# gerbang_fix.net
KiCad netlist of a schematic drawn in EAGLE
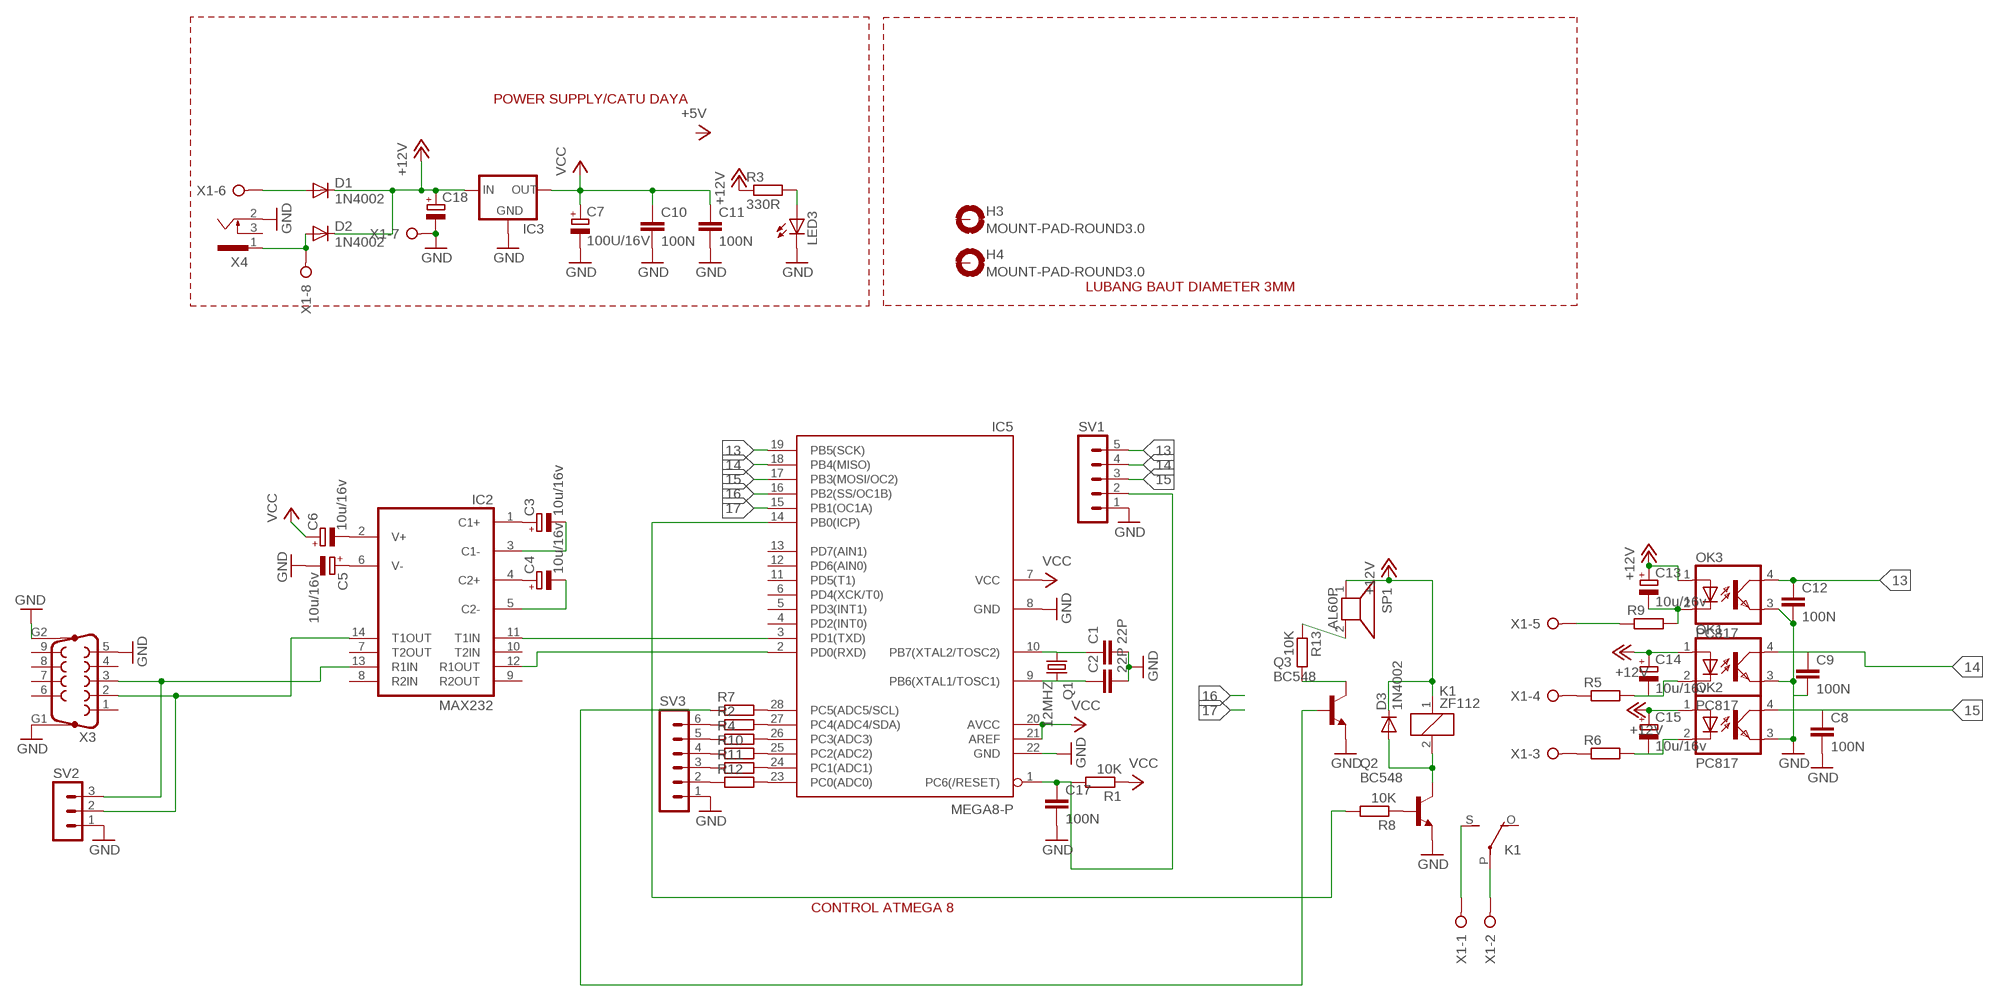
[diagram p0: schematic, sheet 1]

(export (version "E")
  (design (tool "Eeschema 10.0.6"))
  (components
    (comp (ref "C1")
      (value "22P")
      (footprint "eagle-import:C025-025X050")
      (libsource (lib "eagle-import") (part "C-EU025-025X050"))
    )
    (comp (ref "C2")
      (value "22P")
      (footprint "eagle-import:C025-025X050")
      (libsource (lib "eagle-import") (part "C-EU025-025X050"))
    )
    (comp (ref "C3")
      (value "10u/16v")
      (footprint "eagle-import:E2,5-6")
      (libsource (lib "eagle-import") (part "resistor_CPOL-EUE2.5-6"))
    )
    (comp (ref "C4")
      (value "10u/16v")
      (footprint "eagle-import:E2,5-6")
      (libsource (lib "eagle-import") (part "resistor_CPOL-EUE2.5-6"))
    )
    (comp (ref "C5")
      (value "10u/16v")
      (footprint "eagle-import:E2,5-6")
      (libsource (lib "eagle-import") (part "resistor_CPOL-EUE2.5-6"))
    )
    (comp (ref "C6")
      (value "10u/16v")
      (footprint "eagle-import:E2,5-6")
      (libsource (lib "eagle-import") (part "resistor_CPOL-EUE2.5-6"))
    )
    (comp (ref "C7")
      (value "100U/16V")
      (footprint "eagle-import:E2,5-6")
      (libsource (lib "eagle-import") (part "resistor_CPOL-EUE2.5-6"))
    )
    (comp (ref "C8")
      (value "100N")
      (footprint "eagle-import:C025-025X050")
      (libsource (lib "eagle-import") (part "C-EU025-025X050"))
    )
    (comp (ref "C9")
      (value "100N")
      (footprint "eagle-import:C025-025X050")
      (libsource (lib "eagle-import") (part "C-EU025-025X050"))
    )
    (comp (ref "C10")
      (value "100N")
      (footprint "eagle-import:C025-025X050")
      (libsource (lib "eagle-import") (part "C-EU025-025X050"))
    )
    (comp (ref "C11")
      (value "100N")
      (footprint "eagle-import:C025-025X050")
      (libsource (lib "eagle-import") (part "C-EU025-025X050"))
    )
    (comp (ref "C12")
      (value "100N")
      (footprint "eagle-import:C025-025X050")
      (libsource (lib "eagle-import") (part "C-EU025-025X050"))
    )
    (comp (ref "C13")
      (value "10u/16v")
      (footprint "eagle-import:E2,5-6")
      (libsource (lib "eagle-import") (part "resistor_CPOL-EUE2.5-6"))
    )
    (comp (ref "C14")
      (value "10u/16v")
      (footprint "eagle-import:E2,5-6")
      (libsource (lib "eagle-import") (part "resistor_CPOL-EUE2.5-6"))
    )
    (comp (ref "C15")
      (value "10u/16v")
      (footprint "eagle-import:E2,5-6")
      (libsource (lib "eagle-import") (part "resistor_CPOL-EUE2.5-6"))
    )
    (comp (ref "C17")
      (value "100N")
      (footprint "eagle-import:C025-025X050")
      (libsource (lib "eagle-import") (part "C-EU025-025X050"))
    )
    (comp (ref "C18")
      (value "CPOL-EUE5-8.5")
      (footprint "eagle-import:E5-8,5")
      (libsource (lib "eagle-import") (part "CPOL-EUE5-8.5"))
    )
    (comp (ref "D1")
      (value "1N4002")
      (footprint "eagle-import:DO35-10")
      (libsource (lib "eagle-import") (part "1N4148DO35-10"))
    )
    (comp (ref "D2")
      (value "1N4002")
      (footprint "eagle-import:DO35-10")
      (libsource (lib "eagle-import") (part "1N4148DO35-10"))
    )
    (comp (ref "D3")
      (value "1N4002")
      (footprint "eagle-import:DO35-10")
      (libsource (lib "eagle-import") (part "1N4148DO35-10"))
    )
    (comp (ref "H3")
      (value "MOUNT-PAD-ROUND3.0")
      (footprint "eagle-import:3,0-PAD")
      (libsource (lib "eagle-import") (part "MOUNT-PAD-ROUND3.0"))
    )
    (comp (ref "H4")
      (value "MOUNT-PAD-ROUND3.0")
      (footprint "eagle-import:3,0-PAD")
      (libsource (lib "eagle-import") (part "MOUNT-PAD-ROUND3.0"))
    )
    (comp (ref "IC2")
      (value "MAX232")
      (footprint "eagle-import:DIL16")
      (fields (field (name "MF") "MAXIM") (field (name "MPN") "MAX232ACPE+"))
      (libsource (lib "eagle-import") (part "MAX232"))
    )
    (comp (ref "IC3")
      (value "78XXS")
      (footprint "eagle-import:78XXS")
      (libsource (lib "eagle-import") (part "78XXS"))
    )
    (comp (ref "IC5")
      (value "MEGA8-P")
      (footprint "eagle-import:DIL28-3")
      (libsource (lib "eagle-import") (part "MEGA8-P"))
    )
    (comp (ref "K1")
      (value "ZF112")
      (footprint "eagle-import:ZF112")
      (libsource (lib "eagle-import") (part "ZF112"))
    )
    (comp (ref "LED3")
      (value "LED5MM")
      (footprint "eagle-import:LED5MM")
      (libsource (lib "eagle-import") (part "LED5MM"))
    )
    (comp (ref "OK1")
      (value "PC817")
      (footprint "eagle-import:DIL04")
      (fields (field (name "MPN") "PC817X4J000F"))
      (libsource (lib "eagle-import") (part "PC817"))
    )
    (comp (ref "OK2")
      (value "PC817")
      (footprint "eagle-import:DIL04")
      (fields (field (name "MPN") "PC817X4J000F"))
      (libsource (lib "eagle-import") (part "PC817"))
    )
    (comp (ref "OK3")
      (value "PC817")
      (footprint "eagle-import:DIL04")
      (fields (field (name "MPN") "PC817X4J000F"))
      (libsource (lib "eagle-import") (part "PC817"))
    )
    (comp (ref "Q1")
      (value "12MHZ")
      (footprint "eagle-import:HC49U-V")
      (libsource (lib "eagle-import") (part "CRYSTALHC49U-V"))
    )
    (comp (ref "Q2")
      (value "BC548")
      (footprint "eagle-import:TO92-EBC")
      (libsource (lib "eagle-import") (part "BC548"))
    )
    (comp (ref "Q3")
      (value "BC548")
      (footprint "eagle-import:TO92-EBC")
      (libsource (lib "eagle-import") (part "BC548"))
    )
    (comp (ref "R1")
      (value "10K")
      (footprint "eagle-import:0207_10")
      (libsource (lib "eagle-import") (part "resistor_R-EU_0207/10"))
    )
    (comp (ref "R2")
      (value "R-EU_0204/2V")
      (footprint "eagle-import:0204V")
      (libsource (lib "eagle-import") (part "R-EU_0204/2V"))
    )
    (comp (ref "R3")
      (value "330R")
      (footprint "eagle-import:0207_10")
      (libsource (lib "eagle-import") (part "resistor_R-EU_0207/10"))
    )
    (comp (ref "R4")
      (value "R-EU_0204/2V")
      (footprint "eagle-import:0204V")
      (libsource (lib "eagle-import") (part "R-EU_0204/2V"))
    )
    (comp (ref "R5")
      (value "R-EU_0204/2V")
      (footprint "eagle-import:0204V")
      (libsource (lib "eagle-import") (part "R-EU_0204/2V"))
    )
    (comp (ref "R6")
      (value "R-EU_0204/2V")
      (footprint "eagle-import:0204V")
      (libsource (lib "eagle-import") (part "R-EU_0204/2V"))
    )
    (comp (ref "R7")
      (value "R-EU_0204/2V")
      (footprint "eagle-import:0204V")
      (libsource (lib "eagle-import") (part "R-EU_0204/2V"))
    )
    (comp (ref "R8")
      (value "10K")
      (footprint "eagle-import:0207_10")
      (libsource (lib "eagle-import") (part "resistor_R-EU_0207/10"))
    )
    (comp (ref "R9")
      (value "R-EU_0204/2V")
      (footprint "eagle-import:0204V")
      (libsource (lib "eagle-import") (part "R-EU_0204/2V"))
    )
    (comp (ref "R10")
      (value "R-EU_0204/2V")
      (footprint "eagle-import:0204V")
      (libsource (lib "eagle-import") (part "R-EU_0204/2V"))
    )
    (comp (ref "R11")
      (value "R-EU_0204/2V")
      (footprint "eagle-import:0204V")
      (libsource (lib "eagle-import") (part "R-EU_0204/2V"))
    )
    (comp (ref "R12")
      (value "R-EU_0204/2V")
      (footprint "eagle-import:0204V")
      (libsource (lib "eagle-import") (part "R-EU_0204/2V"))
    )
    (comp (ref "R13")
      (value "10K")
      (footprint "eagle-import:0207_10")
      (libsource (lib "eagle-import") (part "resistor_R-EU_0207/10"))
    )
    (comp (ref "SP1")
      (value "AL60P")
      (footprint "eagle-import:AL60P")
      (libsource (lib "eagle-import") (part "AL60P"))
    )
    (comp (ref "SV1")
      (value "MA05-1")
      (footprint "eagle-import:MA05-1")
      (libsource (lib "eagle-import") (part "MA05-1"))
    )
    (comp (ref "SV2")
      (value "MA03-1")
      (footprint "eagle-import:MA03-1")
      (libsource (lib "eagle-import") (part "MA03-1"))
    )
    (comp (ref "SV3")
      (value "MA06-1")
      (footprint "eagle-import:MA06-1")
      (libsource (lib "eagle-import") (part "MA06-1"))
    )
    (comp (ref "X1")
      (value "W237-08P")
      (footprint "eagle-import:W237-8P")
      (libsource (lib "eagle-import") (part "W237-08P"))
    )
    (comp (ref "X3")
      (value "F09HP")
      (footprint "eagle-import:F09HP")
      (libsource (lib "eagle-import") (part "F09HP"))
    )
    (comp (ref "X4")
      (value "733980-62")
      (footprint "eagle-import:733980-62")
      (libsource (lib "eagle-import") (part "73398?0-62"))
    )
  )
  (nets
    (net (code "2") (name "+12V") (class "Default")
      (node (ref "C13") (pin "+") (pinfunction "+_+") (pintype "passive"))
      (node (ref "C14") (pin "+") (pinfunction "+_+") (pintype "passive"))
      (node (ref "C15") (pin "+") (pinfunction "+_+") (pintype "passive"))
      (node (ref "C18") (pin "+") (pinfunction "+_+") (pintype "passive"))
      (node (ref "D1") (pin "C") (pinfunction "C_C") (pintype "passive"))
      (node (ref "D2") (pin "C") (pinfunction "C_C") (pintype "passive"))
      (node (ref "D3") (pin "C") (pinfunction "C_C") (pintype "passive"))
      (node (ref "IC3") (pin "IN") (pinfunction "IN_IN") (pintype "input"))
      (node (ref "K1") (pin "1") (pinfunction "1_1") (pintype "passive"))
      (node (ref "OK1") (pin "1") (pinfunction "A_1") (pintype "passive"))
      (node (ref "OK2") (pin "1") (pinfunction "A_1") (pintype "passive"))
      (node (ref "OK3") (pin "1") (pinfunction "A_1") (pintype "passive"))
      (node (ref "R3") (pin "1") (pinfunction "1_1") (pintype "passive"))
      (node (ref "SP1") (pin "1") (pinfunction "1_1") (pintype "passive"))
    )
    (net (code "3") (name "13") (class "Default")
      (node (ref "C12") (pin "1") (pinfunction "1_1") (pintype "passive"))
      (node (ref "IC5") (pin "19") (pinfunction "PB5(SCK)_19") (pintype "bidirectional"))
      (node (ref "OK3") (pin "4") (pinfunction "COL_4") (pintype "passive"))
      (node (ref "SV1") (pin "5") (pinfunction "5_5") (pintype "passive"))
    )
    (net (code "4") (name "14") (class "Default")
      (node (ref "C9") (pin "1") (pinfunction "1_1") (pintype "passive"))
      (node (ref "IC5") (pin "18") (pinfunction "PB4(MISO)_18") (pintype "bidirectional"))
      (node (ref "OK1") (pin "4") (pinfunction "COL_4") (pintype "passive"))
      (node (ref "SV1") (pin "4") (pinfunction "4_4") (pintype "passive"))
    )
    (net (code "5") (name "15") (class "Default")
      (node (ref "C8") (pin "1") (pinfunction "1_1") (pintype "passive"))
      (node (ref "IC5") (pin "17") (pinfunction "PB3(MOSI/OC2)_17") (pintype "bidirectional"))
      (node (ref "OK2") (pin "4") (pinfunction "COL_4") (pintype "passive"))
      (node (ref "SV1") (pin "3") (pinfunction "3_3") (pintype "passive"))
    )
    (net (code "6") (name "16") (class "Default")
      (node (ref "IC5") (pin "16") (pinfunction "PB2(SS/OC1B)_16") (pintype "bidirectional"))
    )
    (net (code "7") (name "17") (class "Default")
      (node (ref "IC5") (pin "15") (pinfunction "PB1(OC1A)_15") (pintype "bidirectional"))
    )
    (net (code "8") (name "GND") (class "Default")
      (node (ref "C1") (pin "2") (pinfunction "2_2") (pintype "passive"))
      (node (ref "C10") (pin "2") (pinfunction "2_2") (pintype "passive"))
      (node (ref "C11") (pin "2") (pinfunction "2_2") (pintype "passive"))
      (node (ref "C12") (pin "2") (pinfunction "2_2") (pintype "passive"))
      (node (ref "C17") (pin "2") (pinfunction "2_2") (pintype "passive"))
      (node (ref "C18") (pin "-") (pinfunction "-_-") (pintype "passive"))
      (node (ref "C2") (pin "2") (pinfunction "2_2") (pintype "passive"))
      (node (ref "C5") (pin "-") (pinfunction "-_-") (pintype "passive"))
      (node (ref "C7") (pin "-") (pinfunction "-_-") (pintype "passive"))
      (node (ref "C8") (pin "2") (pinfunction "2_2") (pintype "passive"))
      (node (ref "C9") (pin "2") (pinfunction "2_2") (pintype "passive"))
      (node (ref "IC3") (pin "GND") (pinfunction "GND_GND") (pintype "input"))
      (node (ref "IC5") (pin "22") (pinfunction "GND_22") (pintype "power_in"))
      (node (ref "IC5") (pin "8") (pinfunction "GND_8") (pintype "power_in"))
      (node (ref "LED3") (pin "K") (pinfunction "C_K") (pintype "passive"))
      (node (ref "OK1") (pin "3") (pinfunction "EMIT_3") (pintype "passive"))
      (node (ref "OK2") (pin "3") (pinfunction "EMIT_3") (pintype "passive"))
      (node (ref "OK3") (pin "3") (pinfunction "EMIT_3") (pintype "passive"))
      (node (ref "Q2") (pin "E") (pinfunction "E_E") (pintype "passive"))
      (node (ref "Q3") (pin "E") (pinfunction "E_E") (pintype "passive"))
      (node (ref "SV1") (pin "1") (pinfunction "1_1") (pintype "passive"))
      (node (ref "SV2") (pin "1") (pinfunction "1_1") (pintype "passive"))
      (node (ref "SV3") (pin "1") (pinfunction "1_1") (pintype "passive"))
      (node (ref "X1") (pin "7") (pinfunction "KL_7") (pintype "passive"))
      (node (ref "X3") (pin "5") (pinfunction "5_5") (pintype "passive"))
      (node (ref "X3") (pin "G1") (pinfunction "G1_G1") (pintype "passive"))
      (node (ref "X3") (pin "G2") (pinfunction "G2_G2") (pintype "passive"))
      (node (ref "X4") (pin "2") (pinfunction "2_2") (pintype "passive"))
    )
    (net (code "9") (name "Net-(D3-PadA)") (class "Default")
      (node (ref "D3") (pin "A") (pinfunction "A_A") (pintype "passive"))
      (node (ref "K1") (pin "2") (pinfunction "2_2") (pintype "passive"))
      (node (ref "Q2") (pin "C") (pinfunction "C_C") (pintype "passive"))
    )
    (net (code "10") (name "Net-(IC2A-C1+)") (class "Default")
      (node (ref "C3") (pin "+") (pinfunction "+_+") (pintype "passive"))
      (node (ref "IC2") (pin "1") (pinfunction "C1+_1") (pintype "bidirectional"))
    )
    (net (code "11") (name "Net-(IC2A-C1-)") (class "Default")
      (node (ref "C3") (pin "-") (pinfunction "-_-") (pintype "passive"))
      (node (ref "IC2") (pin "3") (pinfunction "C1-_3") (pintype "bidirectional"))
    )
    (net (code "12") (name "Net-(IC2A-C2+)") (class "Default")
      (node (ref "C4") (pin "+") (pinfunction "+_+") (pintype "passive"))
      (node (ref "IC2") (pin "4") (pinfunction "C2+_4") (pintype "bidirectional"))
    )
    (net (code "13") (name "Net-(IC2A-C2-)") (class "Default")
      (node (ref "C4") (pin "-") (pinfunction "-_-") (pintype "passive"))
      (node (ref "IC2") (pin "5") (pinfunction "C2-_5") (pintype "bidirectional"))
    )
    (net (code "14") (name "Net-(IC2A-R1IN)") (class "Default")
      (node (ref "IC2") (pin "13") (pinfunction "R1IN_13") (pintype "input"))
      (node (ref "SV2") (pin "3") (pinfunction "3_3") (pintype "passive"))
      (node (ref "X3") (pin "3") (pinfunction "3_3") (pintype "passive"))
    )
    (net (code "15") (name "Net-(IC2A-R1OUT)") (class "Default")
      (node (ref "IC2") (pin "12") (pinfunction "R1OUT_12") (pintype "output"))
      (node (ref "IC5") (pin "2") (pinfunction "PD0(RXD)_2") (pintype "bidirectional"))
    )
    (net (code "16") (name "Net-(IC2A-T1IN)") (class "Default")
      (node (ref "IC2") (pin "11") (pinfunction "T1IN_11") (pintype "input"))
      (node (ref "IC5") (pin "3") (pinfunction "PD1(TXD)_3") (pintype "bidirectional"))
    )
    (net (code "17") (name "Net-(IC2A-T1OUT)") (class "Default")
      (node (ref "IC2") (pin "14") (pinfunction "T1OUT_14") (pintype "output"))
      (node (ref "SV2") (pin "2") (pinfunction "2_2") (pintype "passive"))
      (node (ref "X3") (pin "2") (pinfunction "2_2") (pintype "passive"))
    )
    (net (code "18") (name "Net-(IC2A-V+)") (class "Default")
      (node (ref "C6") (pin "-") (pinfunction "-_-") (pintype "passive"))
      (node (ref "IC2") (pin "2") (pinfunction "V+_2") (pintype "bidirectional"))
    )
    (net (code "19") (name "Net-(IC2A-V-)") (class "Default")
      (node (ref "C5") (pin "+") (pinfunction "+_+") (pintype "passive"))
      (node (ref "IC2") (pin "6") (pinfunction "V-_6") (pintype "bidirectional"))
    )
    (net (code "20") (name "Net-(IC5-PB0(ICP))") (class "Default")
      (node (ref "IC5") (pin "14") (pinfunction "PB0(ICP)_14") (pintype "bidirectional"))
      (node (ref "R8") (pin "2") (pinfunction "2_2") (pintype "passive"))
    )
    (net (code "21") (name "Net-(IC5-PB6(XTAL1{slash}TOSC1))") (class "Default")
      (node (ref "C2") (pin "1") (pinfunction "1_1") (pintype "passive"))
      (node (ref "IC5") (pin "9") (pinfunction "PB6(XTAL1/TOSC1)_9") (pintype "bidirectional"))
      (node (ref "Q1") (pin "2") (pinfunction "2_2") (pintype "passive"))
    )
    (net (code "22") (name "Net-(IC5-PB7(XTAL2{slash}TOSC2))") (class "Default")
      (node (ref "C1") (pin "1") (pinfunction "1_1") (pintype "passive"))
      (node (ref "IC5") (pin "10") (pinfunction "PB7(XTAL2/TOSC2)_10") (pintype "bidirectional"))
      (node (ref "Q1") (pin "1") (pinfunction "1_1") (pintype "passive"))
    )
    (net (code "23") (name "Net-(IC5-PC0(ADC0))") (class "Default")
      (node (ref "IC5") (pin "23") (pinfunction "PC0(ADC0)_23") (pintype "bidirectional"))
      (node (ref "R12") (pin "2") (pinfunction "2_2") (pintype "passive"))
    )
    (net (code "24") (name "Net-(IC5-PC1(ADC1))") (class "Default")
      (node (ref "IC5") (pin "24") (pinfunction "PC1(ADC1)_24") (pintype "bidirectional"))
      (node (ref "R11") (pin "2") (pinfunction "2_2") (pintype "passive"))
    )
    (net (code "25") (name "Net-(IC5-PC2(ADC2))") (class "Default")
      (node (ref "IC5") (pin "25") (pinfunction "PC2(ADC2)_25") (pintype "bidirectional"))
      (node (ref "R10") (pin "2") (pinfunction "2_2") (pintype "passive"))
    )
    (net (code "26") (name "Net-(IC5-PC3(ADC3))") (class "Default")
      (node (ref "IC5") (pin "26") (pinfunction "PC3(ADC3)_26") (pintype "bidirectional"))
      (node (ref "R4") (pin "2") (pinfunction "2_2") (pintype "passive"))
    )
    (net (code "27") (name "Net-(IC5-PC4(ADC4{slash}SDA))") (class "Default")
      (node (ref "IC5") (pin "27") (pinfunction "PC4(ADC4/SDA)_27") (pintype "bidirectional"))
      (node (ref "R2") (pin "2") (pinfunction "2_2") (pintype "passive"))
    )
    (net (code "28") (name "Net-(IC5-PC5(ADC5{slash}SCL))") (class "Default")
      (node (ref "IC5") (pin "28") (pinfunction "PC5(ADC5/SCL)_28") (pintype "bidirectional"))
      (node (ref "R7") (pin "2") (pinfunction "2_2") (pintype "passive"))
    )
    (net (code "29") (name "Net-(IC5-PC6({slash}RESET))") (class "Default")
      (node (ref "C17") (pin "1") (pinfunction "1_1") (pintype "passive"))
      (node (ref "IC5") (pin "1") (pinfunction "PC6(/RESET)_1") (pintype "bidirectional"))
      (node (ref "R1") (pin "2") (pinfunction "2_2") (pintype "passive"))
      (node (ref "SV1") (pin "2") (pinfunction "2_2") (pintype "passive"))
    )
    (net (code "30") (name "Net-(LED3-PadA)") (class "Default")
      (node (ref "LED3") (pin "A") (pinfunction "A_A") (pintype "passive"))
      (node (ref "R3") (pin "2") (pinfunction "2_2") (pintype "passive"))
    )
    (net (code "31") (name "Net-(OK1-C)") (class "Default")
      (node (ref "C14") (pin "-") (pinfunction "-_-") (pintype "passive"))
      (node (ref "OK1") (pin "2") (pinfunction "C_2") (pintype "passive"))
      (node (ref "R5") (pin "2") (pinfunction "2_2") (pintype "passive"))
    )
    (net (code "32") (name "Net-(OK2-C)") (class "Default")
      (node (ref "C15") (pin "-") (pinfunction "-_-") (pintype "passive"))
      (node (ref "OK2") (pin "2") (pinfunction "C_2") (pintype "passive"))
      (node (ref "R6") (pin "2") (pinfunction "2_2") (pintype "passive"))
    )
    (net (code "33") (name "Net-(OK3-C)") (class "Default")
      (node (ref "C13") (pin "-") (pinfunction "-_-") (pintype "passive"))
      (node (ref "OK3") (pin "2") (pinfunction "C_2") (pintype "passive"))
      (node (ref "R9") (pin "2") (pinfunction "2_2") (pintype "passive"))
    )
    (net (code "34") (name "Net-(Q2-PadB)") (class "Default")
      (node (ref "Q2") (pin "B") (pinfunction "B_B") (pintype "passive"))
      (node (ref "R8") (pin "1") (pinfunction "1_1") (pintype "passive"))
    )
    (net (code "35") (name "Net-(Q3-PadB)") (class "Default")
      (node (ref "Q3") (pin "B") (pinfunction "B_B") (pintype "passive"))
      (node (ref "R7") (pin "1") (pinfunction "1_1") (pintype "passive"))
    )
    (net (code "36") (name "Net-(Q3-PadC)") (class "Default")
      (node (ref "Q3") (pin "C") (pinfunction "C_C") (pintype "passive"))
      (node (ref "R13") (pin "2") (pinfunction "2_2") (pintype "passive"))
    )
    (net (code "37") (name "Net-(R2-Pad1)") (class "Default")
      (node (ref "R2") (pin "1") (pinfunction "1_1") (pintype "passive"))
      (node (ref "SV3") (pin "6") (pinfunction "6_6") (pintype "passive"))
    )
    (net (code "38") (name "Net-(R4-Pad1)") (class "Default")
      (node (ref "R4") (pin "1") (pinfunction "1_1") (pintype "passive"))
      (node (ref "SV3") (pin "5") (pinfunction "5_5") (pintype "passive"))
    )
    (net (code "39") (name "Net-(R10-Pad1)") (class "Default")
      (node (ref "R10") (pin "1") (pinfunction "1_1") (pintype "passive"))
      (node (ref "SV3") (pin "4") (pinfunction "4_4") (pintype "passive"))
    )
    (net (code "40") (name "Net-(R11-Pad1)") (class "Default")
      (node (ref "R11") (pin "1") (pinfunction "1_1") (pintype "passive"))
      (node (ref "SV3") (pin "3") (pinfunction "3_3") (pintype "passive"))
    )
    (net (code "41") (name "Net-(R12-Pad1)") (class "Default")
      (node (ref "R12") (pin "1") (pinfunction "1_1") (pintype "passive"))
      (node (ref "SV3") (pin "2") (pinfunction "2_2") (pintype "passive"))
    )
    (net (code "42") (name "Net-(R13-Pad1)") (class "Default")
      (node (ref "R13") (pin "1") (pinfunction "1_1") (pintype "passive"))
      (node (ref "SP1") (pin "2") (pinfunction "2_2") (pintype "passive"))
    )
    (net (code "43") (name "Net-(X1A-KL)") (class "Default")
      (node (ref "K1") (pin "S") (pinfunction "S_S") (pintype "passive"))
      (node (ref "X1") (pin "1") (pinfunction "KL_1") (pintype "passive"))
    )
    (net (code "44") (name "Net-(X1B-KL)") (class "Default")
      (node (ref "K1") (pin "P") (pinfunction "P_P") (pintype "passive"))
      (node (ref "X1") (pin "2") (pinfunction "KL_2") (pintype "passive"))
    )
    (net (code "45") (name "Net-(X1C-KL)") (class "Default")
      (node (ref "R6") (pin "1") (pinfunction "1_1") (pintype "passive"))
      (node (ref "X1") (pin "3") (pinfunction "KL_3") (pintype "passive"))
    )
    (net (code "46") (name "Net-(X1D-KL)") (class "Default")
      (node (ref "R5") (pin "1") (pinfunction "1_1") (pintype "passive"))
      (node (ref "X1") (pin "4") (pinfunction "KL_4") (pintype "passive"))
    )
    (net (code "47") (name "Net-(X1E-KL)") (class "Default")
      (node (ref "R9") (pin "1") (pinfunction "1_1") (pintype "passive"))
      (node (ref "X1") (pin "5") (pinfunction "KL_5") (pintype "passive"))
    )
    (net (code "48") (name "Net-(X1F-KL)") (class "Default")
      (node (ref "D1") (pin "A") (pinfunction "A_A") (pintype "passive"))
      (node (ref "X1") (pin "6") (pinfunction "KL_6") (pintype "passive"))
    )
    (net (code "49") (name "Net-(X1H-KL)") (class "Default")
      (node (ref "D2") (pin "A") (pinfunction "A_A") (pintype "passive"))
      (node (ref "X1") (pin "8") (pinfunction "KL_8") (pintype "passive"))
      (node (ref "X4") (pin "1") (pinfunction "1_1") (pintype "passive"))
    )
    (net (code "50") (name "VCC") (class "Default")
      (node (ref "C10") (pin "1") (pinfunction "1_1") (pintype "passive"))
      (node (ref "C11") (pin "1") (pinfunction "1_1") (pintype "passive"))
      (node (ref "C6") (pin "+") (pinfunction "+_+") (pintype "passive"))
      (node (ref "C7") (pin "+") (pinfunction "+_+") (pintype "passive"))
      (node (ref "IC3") (pin "OUT") (pinfunction "OUT_OUT") (pintype "passive"))
      (node (ref "IC5") (pin "20") (pinfunction "AVCC_20") (pintype "power_in"))
      (node (ref "IC5") (pin "21") (pinfunction "AREF_21") (pintype "passive"))
      (node (ref "IC5") (pin "7") (pinfunction "VCC_7") (pintype "power_in"))
      (node (ref "R1") (pin "1") (pinfunction "1_1") (pintype "passive"))
    )
    (net (code "51") (name "unconnected-(H3-MOUNT-PadB3,0)") (class "Default")
      (node (ref "H3") (pin "B3,0") (pinfunction "MOUNT_B3,0") (pintype "passive"))
    )
    (net (code "52") (name "unconnected-(H4-MOUNT-PadB3,0)") (class "Default")
      (node (ref "H4") (pin "B3,0") (pinfunction "MOUNT_B3,0") (pintype "passive"))
    )
    (net (code "53") (name "unconnected-(IC2A-R2IN-Pad8)") (class "Default")
      (node (ref "IC2") (pin "8") (pinfunction "R2IN_8") (pintype "input"))
    )
    (net (code "54") (name "unconnected-(IC2A-R2OUT-Pad9)") (class "Default")
      (node (ref "IC2") (pin "9") (pinfunction "R2OUT_9") (pintype "output"))
    )
    (net (code "55") (name "unconnected-(IC2A-T2IN-Pad10)") (class "Default")
      (node (ref "IC2") (pin "10") (pinfunction "T2IN_10") (pintype "input"))
    )
    (net (code "56") (name "unconnected-(IC2A-T2OUT-Pad7)") (class "Default")
      (node (ref "IC2") (pin "7") (pinfunction "T2OUT_7") (pintype "output"))
    )
    (net (code "57") (name "unconnected-(IC5-PD2(INT0)-Pad4)") (class "Default")
      (node (ref "IC5") (pin "4") (pinfunction "PD2(INT0)_4") (pintype "bidirectional"))
    )
    (net (code "58") (name "unconnected-(IC5-PD3(INT1)-Pad5)") (class "Default")
      (node (ref "IC5") (pin "5") (pinfunction "PD3(INT1)_5") (pintype "bidirectional"))
    )
    (net (code "59") (name "unconnected-(IC5-PD4(XCK{slash}T0)-Pad6)") (class "Default")
      (node (ref "IC5") (pin "6") (pinfunction "PD4(XCK/T0)_6") (pintype "bidirectional"))
    )
    (net (code "60") (name "unconnected-(IC5-PD5(T1)-Pad11)") (class "Default")
      (node (ref "IC5") (pin "11") (pinfunction "PD5(T1)_11") (pintype "bidirectional"))
    )
    (net (code "61") (name "unconnected-(IC5-PD6(AIN0)-Pad12)") (class "Default")
      (node (ref "IC5") (pin "12") (pinfunction "PD6(AIN0)_12") (pintype "bidirectional"))
    )
    (net (code "62") (name "unconnected-(IC5-PD7(AIN1)-Pad13)") (class "Default")
      (node (ref "IC5") (pin "13") (pinfunction "PD7(AIN1)_13") (pintype "bidirectional"))
    )
    (net (code "63") (name "unconnected-(K1-PadO)") (class "Default")
      (node (ref "K1") (pin "O") (pinfunction "O_O") (pintype "passive"))
    )
    (net (code "64") (name "unconnected-(X3-Pad1)") (class "Default")
      (node (ref "X3") (pin "1") (pinfunction "1_1") (pintype "passive"))
    )
    (net (code "65") (name "unconnected-(X3-Pad4)") (class "Default")
      (node (ref "X3") (pin "4") (pinfunction "4_4") (pintype "passive"))
    )
    (net (code "66") (name "unconnected-(X3-Pad6)") (class "Default")
      (node (ref "X3") (pin "6") (pinfunction "6_6") (pintype "passive"))
    )
    (net (code "67") (name "unconnected-(X3-Pad7)") (class "Default")
      (node (ref "X3") (pin "7") (pinfunction "7_7") (pintype "passive"))
    )
    (net (code "68") (name "unconnected-(X3-Pad8)") (class "Default")
      (node (ref "X3") (pin "8") (pinfunction "8_8") (pintype "passive"))
    )
    (net (code "69") (name "unconnected-(X3-Pad9)") (class "Default")
      (node (ref "X3") (pin "9") (pinfunction "9_9") (pintype "passive"))
    )
    (net (code "70") (name "unconnected-(X4-Pad3)") (class "Default")
      (node (ref "X4") (pin "3") (pinfunction "3_3") (pintype "passive"))
    )
  )
)
